# CustomIO.net
KiCad netlist of a schematic drawn in EAGLE
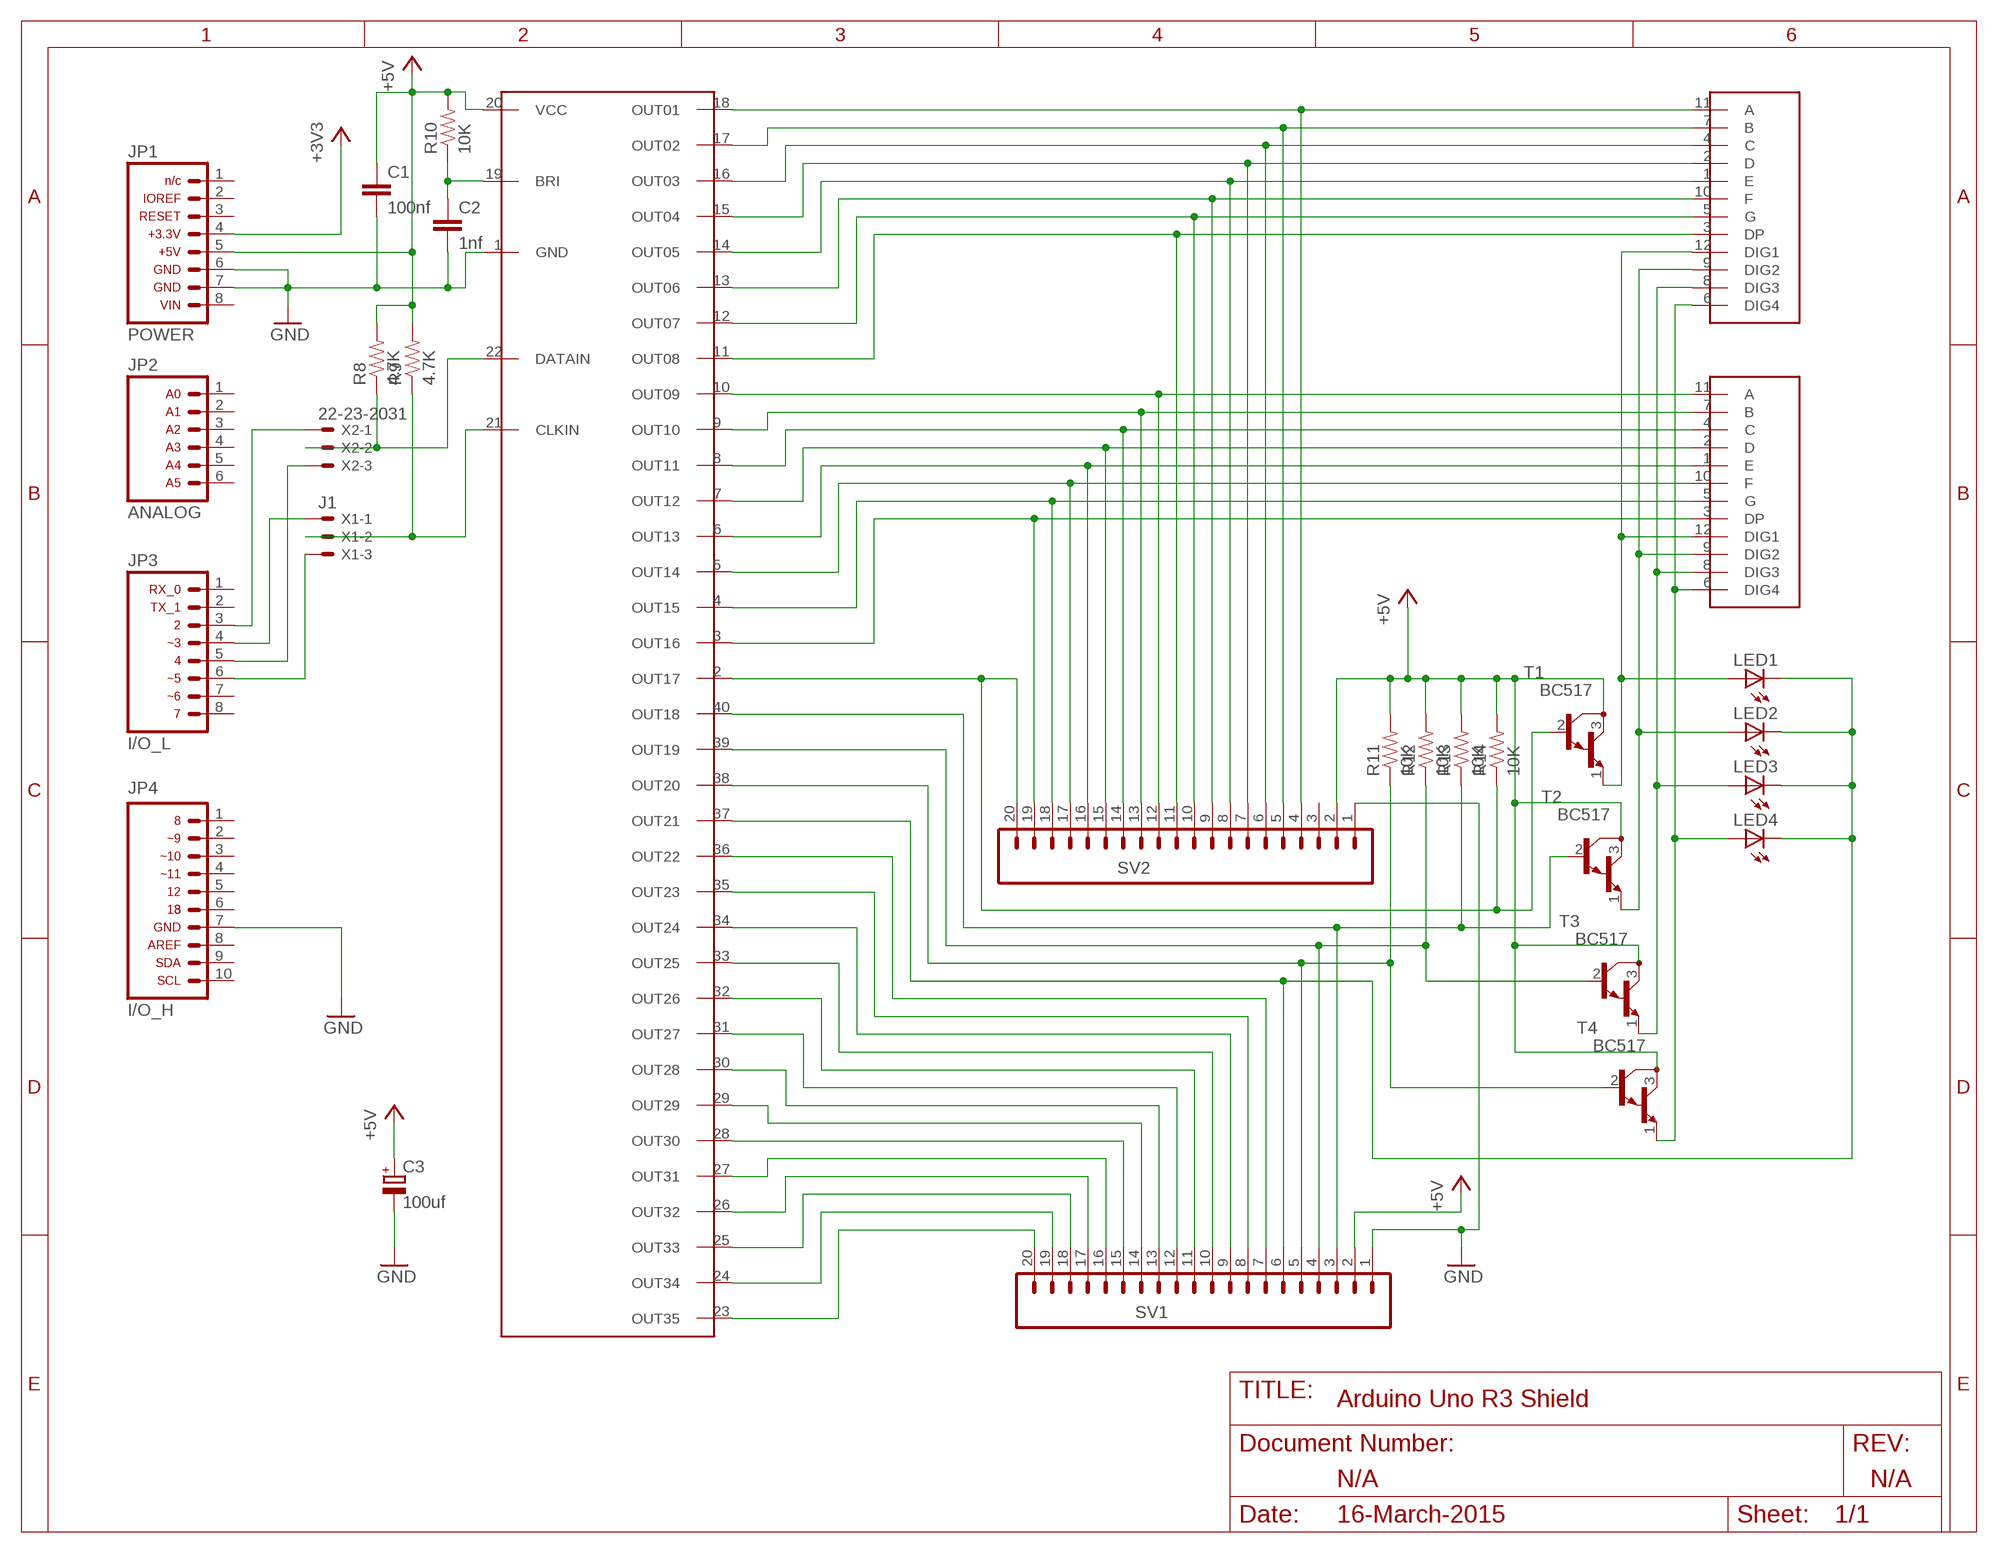
[diagram p0: schematic, sheet 1]

(export (version "E")
  (design (tool "Eeschema 10.0.6"))
  (components
    (comp (ref "C1")
      (value "100nf")
      (footprint "eagle-import:C2.5-4")
      (libsource (lib "eagle-import") (part "C2.5/4"))
    )
    (comp (ref "C2")
      (value "1nf")
      (footprint "eagle-import:C5B2.5")
      (libsource (lib "eagle-import") (part "C5/2.5"))
    )
    (comp (ref "C3")
      (value "100uf")
      (footprint "eagle-import:E2,5-7---100UF")
      (libsource (lib "eagle-import") (part "CPOL1"))
    )
    (comp (ref "JP1")
      (value "ARDUINO_CONN-POWERSIP")
      (footprint "eagle-import:CONN-1X08")
      (libsource (lib "eagle-import") (part "ARDUINO_CONN-POWERSIP"))
    )
    (comp (ref "JP2")
      (value "ARDUINO_CONN-ANALOGSIP")
      (footprint "eagle-import:CONN-1X06")
      (libsource (lib "eagle-import") (part "ARDUINO_CONN-ANALOGSIP"))
    )
    (comp (ref "JP3")
      (value "ARDUINO_CONN-IO_LSIP")
      (footprint "eagle-import:CONN-1X08")
      (libsource (lib "eagle-import") (part "ARDUINO_CONN-IO_LSIP"))
    )
    (comp (ref "JP4")
      (value "ARDUINO_CONN-IO_HSIP")
      (footprint "eagle-import:CONN-1X10")
      (libsource (lib "eagle-import") (part "ARDUINO_CONN-IO_HSIP"))
    )
    (comp (ref "LED1")
      (value "LED3MM")
      (footprint "eagle-import:HLMP-D105")
      (libsource (lib "eagle-import") (part "LED3MM"))
    )
    (comp (ref "LED2")
      (value "LED3MM")
      (footprint "eagle-import:HLMP-D105")
      (libsource (lib "eagle-import") (part "LED3MM"))
    )
    (comp (ref "LED3")
      (value "LED3MM")
      (footprint "eagle-import:HLMP-D105")
      (libsource (lib "eagle-import") (part "LED3MM"))
    )
    (comp (ref "LED4")
      (value "LED3MM")
      (footprint "eagle-import:HLMP-D105")
      (libsource (lib "eagle-import") (part "LED3MM"))
    )
    (comp (ref "R8")
      (value "4.7K")
      (footprint "eagle-import:AXIAL-0.3-KIT")
      (libsource (lib "eagle-import") (part "10KOHM1/6W5%(PTH)KIT"))
    )
    (comp (ref "R9")
      (value "4.7K")
      (footprint "eagle-import:AXIAL-0.3-KIT")
      (libsource (lib "eagle-import") (part "10KOHM1/6W5%(PTH)KIT"))
    )
    (comp (ref "R10")
      (value "10K")
      (footprint "eagle-import:AXIAL-0.3-KIT")
      (libsource (lib "eagle-import") (part "10KOHM1/6W5%(PTH)KIT"))
    )
    (comp (ref "R11")
      (value "10K")
      (footprint "eagle-import:AXIAL-0.3-KIT")
      (libsource (lib "eagle-import") (part "10KOHM1/6W5%(PTH)KIT"))
    )
    (comp (ref "R12")
      (value "10K")
      (footprint "eagle-import:AXIAL-0.3-KIT")
      (libsource (lib "eagle-import") (part "10KOHM1/6W5%(PTH)KIT"))
    )
    (comp (ref "R13")
      (value "10K")
      (footprint "eagle-import:AXIAL-0.3-KIT")
      (libsource (lib "eagle-import") (part "10KOHM1/6W5%(PTH)KIT"))
    )
    (comp (ref "R14")
      (value "10K")
      (footprint "eagle-import:AXIAL-0.3-KIT")
      (libsource (lib "eagle-import") (part "10KOHM1/6W5%(PTH)KIT"))
    )
    (comp (ref "SV1")
      (value "MA10-2")
      (footprint "eagle-import:MA10-2")
      (libsource (lib "eagle-import") (part "MA10-2"))
    )
    (comp (ref "SV2")
      (value "MA10-2")
      (footprint "eagle-import:MA10-2")
      (libsource (lib "eagle-import") (part "MA10-2"))
    )
    (comp (ref "T1")
      (value "BC517")
      (footprint "eagle-import:TO92")
      (libsource (lib "eagle-import") (part "BC517"))
    )
    (comp (ref "T2")
      (value "BC517")
      (footprint "eagle-import:TO92")
      (libsource (lib "eagle-import") (part "BC517"))
    )
    (comp (ref "T3")
      (value "BC517")
      (footprint "eagle-import:TO92")
      (libsource (lib "eagle-import") (part "BC517"))
    )
    (comp (ref "T4")
      (value "BC517")
      (footprint "eagle-import:TO92")
      (libsource (lib "eagle-import") (part "BC517"))
    )
    (comp (ref "U$1")
      (value "ST-M5451PDIP40")
      (footprint "eagle-import:DIL40")
      (libsource (lib "eagle-import") (part "ST-M5451PDIP40"))
    )
    (comp (ref "U$2")
      (value "LDS-3461BXTHURHOLE")
      (footprint "eagle-import:LDS-3461BX")
      (libsource (lib "eagle-import") (part "LDS-3461BXTHURHOLE"))
    )
    (comp (ref "U$3")
      (value "LDS-3461BXTHURHOLE")
      (footprint "eagle-import:LDS-3461BX")
      (libsource (lib "eagle-import") (part "LDS-3461BXTHURHOLE"))
    )
    (comp (ref "X1")
      (value "J1")
      (footprint "eagle-import:22-23-2031")
      (fields (field (name "MF") "MOLEX") (field (name "MPN") "22-23-2031"))
      (libsource (lib "eagle-import") (part "22-23-2031"))
    )
    (comp (ref "X2")
      (value "22-23-2031")
      (footprint "eagle-import:22-23-2031")
      (fields (field (name "MF") "MOLEX"))
      (libsource (lib "eagle-import") (part "22-23-2031"))
    )
  )
  (nets
    (net (code "1") (name "+3V3") (class "Default")
      (node (ref "JP1") (pin "4") (pinfunction "4_4") (pintype "passive"))
    )
    (net (code "2") (name "+5V") (class "Default")
      (node (ref "C1") (pin "1") (pinfunction "1_1") (pintype "passive"))
      (node (ref "C3") (pin "+") (pinfunction "+_+") (pintype "passive"))
      (node (ref "JP1") (pin "5") (pinfunction "5_5") (pintype "passive"))
      (node (ref "R10") (pin "P$2") (pinfunction "2_P$2") (pintype "passive"))
      (node (ref "R11") (pin "P$2") (pinfunction "2_P$2") (pintype "passive"))
      (node (ref "R12") (pin "P$2") (pinfunction "2_P$2") (pintype "passive"))
      (node (ref "R13") (pin "P$2") (pinfunction "2_P$2") (pintype "passive"))
      (node (ref "R14") (pin "P$2") (pinfunction "2_P$2") (pintype "passive"))
      (node (ref "R8") (pin "P$2") (pinfunction "2_P$2") (pintype "passive"))
      (node (ref "R9") (pin "P$2") (pinfunction "2_P$2") (pintype "passive"))
      (node (ref "SV1") (pin "2") (pinfunction "2_2") (pintype "passive"))
      (node (ref "SV2") (pin "2") (pinfunction "2_2") (pintype "passive"))
      (node (ref "T1") (pin "3") (pinfunction "C_3") (pintype "passive"))
      (node (ref "T2") (pin "3") (pinfunction "C_3") (pintype "passive"))
      (node (ref "T3") (pin "3") (pinfunction "C_3") (pintype "passive"))
      (node (ref "T4") (pin "3") (pinfunction "C_3") (pintype "passive"))
      (node (ref "U$1") (pin "20") (pinfunction "VCC_20") (pintype "bidirectional"))
    )
    (net (code "3") (name "GND") (class "Default")
      (node (ref "C1") (pin "2") (pinfunction "2_2") (pintype "passive"))
      (node (ref "C2") (pin "2") (pinfunction "2_2") (pintype "passive"))
      (node (ref "C3") (pin "-") (pinfunction "-_-") (pintype "passive"))
      (node (ref "JP1") (pin "6") (pinfunction "6_6") (pintype "passive"))
      (node (ref "JP1") (pin "7") (pinfunction "7_7") (pintype "passive"))
      (node (ref "JP4") (pin "7") (pinfunction "7_7") (pintype "passive"))
      (node (ref "SV1") (pin "1") (pinfunction "1_1") (pintype "passive"))
      (node (ref "SV2") (pin "1") (pinfunction "1_1") (pintype "passive"))
      (node (ref "U$1") (pin "1") (pinfunction "GND_1") (pintype "bidirectional"))
    )
    (net (code "4") (name "Net-(LED1-C)") (class "Default")
      (node (ref "LED1") (pin "K") (pinfunction "C_K") (pintype "passive"))
      (node (ref "LED2") (pin "K") (pinfunction "C_K") (pintype "passive"))
      (node (ref "LED3") (pin "K") (pinfunction "C_K") (pintype "passive"))
      (node (ref "LED4") (pin "K") (pinfunction "C_K") (pintype "passive"))
      (node (ref "SV1") (pin "6") (pinfunction "6_6") (pintype "passive"))
      (node (ref "U$1") (pin "37") (pinfunction "OUT21_37") (pintype "bidirectional"))
    )
    (net (code "5") (name "Net-(R8-1)") (class "Default")
      (node (ref "R8") (pin "P$1") (pinfunction "1_P$1") (pintype "passive"))
      (node (ref "U$1") (pin "22") (pinfunction "DATAIN_22") (pintype "bidirectional"))
      (node (ref "X2") (pin "2") (pinfunction "S_2") (pintype "passive"))
    )
    (net (code "6") (name "Net-(R9-1)") (class "Default")
      (node (ref "R9") (pin "P$1") (pinfunction "1_P$1") (pintype "passive"))
      (node (ref "U$1") (pin "21") (pinfunction "CLKIN_21") (pintype "bidirectional"))
      (node (ref "X1") (pin "2") (pinfunction "S_2") (pintype "passive"))
    )
    (net (code "7") (name "Net-(R10-1)") (class "Default")
      (node (ref "C2") (pin "1") (pinfunction "1_1") (pintype "passive"))
      (node (ref "R10") (pin "P$1") (pinfunction "1_P$1") (pintype "passive"))
      (node (ref "U$1") (pin "19") (pinfunction "BRI_19") (pintype "bidirectional"))
    )
    (net (code "8") (name "Net-(R11-1)") (class "Default")
      (node (ref "R11") (pin "P$1") (pinfunction "1_P$1") (pintype "passive"))
      (node (ref "SV1") (pin "5") (pinfunction "5_5") (pintype "passive"))
      (node (ref "T4") (pin "2") (pinfunction "B_2") (pintype "passive"))
      (node (ref "U$1") (pin "38") (pinfunction "OUT20_38") (pintype "bidirectional"))
    )
    (net (code "9") (name "Net-(R12-1)") (class "Default")
      (node (ref "R12") (pin "P$1") (pinfunction "1_P$1") (pintype "passive"))
      (node (ref "SV1") (pin "4") (pinfunction "4_4") (pintype "passive"))
      (node (ref "T3") (pin "2") (pinfunction "B_2") (pintype "passive"))
      (node (ref "U$1") (pin "39") (pinfunction "OUT19_39") (pintype "bidirectional"))
    )
    (net (code "10") (name "Net-(R13-1)") (class "Default")
      (node (ref "R13") (pin "P$1") (pinfunction "1_P$1") (pintype "passive"))
      (node (ref "SV1") (pin "3") (pinfunction "3_3") (pintype "passive"))
      (node (ref "T2") (pin "2") (pinfunction "B_2") (pintype "passive"))
      (node (ref "U$1") (pin "40") (pinfunction "OUT18_40") (pintype "bidirectional"))
    )
    (net (code "11") (name "Net-(R14-1)") (class "Default")
      (node (ref "R14") (pin "P$1") (pinfunction "1_P$1") (pintype "passive"))
      (node (ref "SV2") (pin "20") (pinfunction "20_20") (pintype "passive"))
      (node (ref "T1") (pin "2") (pinfunction "B_2") (pintype "passive"))
      (node (ref "U$1") (pin "2") (pinfunction "OUT17_2") (pintype "bidirectional"))
    )
    (net (code "12") (name "Net-(T1-E)") (class "Default")
      (node (ref "LED1") (pin "A") (pinfunction "A_A") (pintype "passive"))
      (node (ref "T1") (pin "1") (pinfunction "E_1") (pintype "passive"))
      (node (ref "U$2") (pin "12") (pinfunction "DIG1_12") (pintype "bidirectional"))
      (node (ref "U$3") (pin "12") (pinfunction "DIG1_12") (pintype "bidirectional"))
    )
    (net (code "13") (name "Net-(T2-E)") (class "Default")
      (node (ref "LED2") (pin "A") (pinfunction "A_A") (pintype "passive"))
      (node (ref "T2") (pin "1") (pinfunction "E_1") (pintype "passive"))
      (node (ref "U$2") (pin "9") (pinfunction "DIG2_9") (pintype "bidirectional"))
      (node (ref "U$3") (pin "9") (pinfunction "DIG2_9") (pintype "bidirectional"))
    )
    (net (code "14") (name "Net-(T3-E)") (class "Default")
      (node (ref "LED3") (pin "A") (pinfunction "A_A") (pintype "passive"))
      (node (ref "T3") (pin "1") (pinfunction "E_1") (pintype "passive"))
      (node (ref "U$2") (pin "8") (pinfunction "DIG3_8") (pintype "bidirectional"))
      (node (ref "U$3") (pin "8") (pinfunction "DIG3_8") (pintype "bidirectional"))
    )
    (net (code "15") (name "Net-(T4-E)") (class "Default")
      (node (ref "LED4") (pin "A") (pinfunction "A_A") (pintype "passive"))
      (node (ref "T4") (pin "1") (pinfunction "E_1") (pintype "passive"))
      (node (ref "U$2") (pin "6") (pinfunction "DIG4_6") (pintype "bidirectional"))
      (node (ref "U$3") (pin "6") (pinfunction "DIG4_6") (pintype "bidirectional"))
    )
    (net (code "16") (name "Net-(U$1C-OUT01)") (class "Default")
      (node (ref "SV2") (pin "4") (pinfunction "4_4") (pintype "passive"))
      (node (ref "U$1") (pin "18") (pinfunction "OUT01_18") (pintype "bidirectional"))
      (node (ref "U$2") (pin "11") (pinfunction "A_11") (pintype "bidirectional"))
    )
    (net (code "17") (name "Net-(U$1C-OUT02)") (class "Default")
      (node (ref "SV2") (pin "5") (pinfunction "5_5") (pintype "passive"))
      (node (ref "U$1") (pin "17") (pinfunction "OUT02_17") (pintype "bidirectional"))
      (node (ref "U$2") (pin "7") (pinfunction "B_7") (pintype "bidirectional"))
    )
    (net (code "18") (name "Net-(U$1C-OUT03)") (class "Default")
      (node (ref "SV2") (pin "6") (pinfunction "6_6") (pintype "passive"))
      (node (ref "U$1") (pin "16") (pinfunction "OUT03_16") (pintype "bidirectional"))
      (node (ref "U$2") (pin "4") (pinfunction "C_4") (pintype "bidirectional"))
    )
    (net (code "19") (name "Net-(U$1C-OUT04)") (class "Default")
      (node (ref "SV2") (pin "7") (pinfunction "7_7") (pintype "passive"))
      (node (ref "U$1") (pin "15") (pinfunction "OUT04_15") (pintype "bidirectional"))
      (node (ref "U$2") (pin "2") (pinfunction "D_2") (pintype "bidirectional"))
    )
    (net (code "20") (name "Net-(U$1C-OUT05)") (class "Default")
      (node (ref "SV2") (pin "8") (pinfunction "8_8") (pintype "passive"))
      (node (ref "U$1") (pin "14") (pinfunction "OUT05_14") (pintype "bidirectional"))
      (node (ref "U$2") (pin "1") (pinfunction "E_1") (pintype "bidirectional"))
    )
    (net (code "21") (name "Net-(U$1C-OUT06)") (class "Default")
      (node (ref "SV2") (pin "9") (pinfunction "9_9") (pintype "passive"))
      (node (ref "U$1") (pin "13") (pinfunction "OUT06_13") (pintype "bidirectional"))
      (node (ref "U$2") (pin "10") (pinfunction "F_10") (pintype "bidirectional"))
    )
    (net (code "22") (name "Net-(U$1C-OUT07)") (class "Default")
      (node (ref "SV2") (pin "10") (pinfunction "10_10") (pintype "passive"))
      (node (ref "U$1") (pin "12") (pinfunction "OUT07_12") (pintype "bidirectional"))
      (node (ref "U$2") (pin "5") (pinfunction "G_5") (pintype "bidirectional"))
    )
    (net (code "23") (name "Net-(U$1C-OUT08)") (class "Default")
      (node (ref "SV2") (pin "11") (pinfunction "11_11") (pintype "passive"))
      (node (ref "U$1") (pin "11") (pinfunction "OUT08_11") (pintype "bidirectional"))
      (node (ref "U$2") (pin "3") (pinfunction "DP_3") (pintype "bidirectional"))
    )
    (net (code "24") (name "Net-(U$1C-OUT09)") (class "Default")
      (node (ref "SV2") (pin "12") (pinfunction "12_12") (pintype "passive"))
      (node (ref "U$1") (pin "10") (pinfunction "OUT09_10") (pintype "bidirectional"))
      (node (ref "U$3") (pin "11") (pinfunction "A_11") (pintype "bidirectional"))
    )
    (net (code "25") (name "Net-(U$1C-OUT10)") (class "Default")
      (node (ref "SV2") (pin "13") (pinfunction "13_13") (pintype "passive"))
      (node (ref "U$1") (pin "9") (pinfunction "OUT10_9") (pintype "bidirectional"))
      (node (ref "U$3") (pin "7") (pinfunction "B_7") (pintype "bidirectional"))
    )
    (net (code "26") (name "Net-(U$1C-OUT11)") (class "Default")
      (node (ref "SV2") (pin "14") (pinfunction "14_14") (pintype "passive"))
      (node (ref "U$1") (pin "8") (pinfunction "OUT11_8") (pintype "bidirectional"))
      (node (ref "U$3") (pin "4") (pinfunction "C_4") (pintype "bidirectional"))
    )
    (net (code "27") (name "Net-(U$1C-OUT12)") (class "Default")
      (node (ref "SV2") (pin "15") (pinfunction "15_15") (pintype "passive"))
      (node (ref "U$1") (pin "7") (pinfunction "OUT12_7") (pintype "bidirectional"))
      (node (ref "U$3") (pin "2") (pinfunction "D_2") (pintype "bidirectional"))
    )
    (net (code "28") (name "Net-(U$1C-OUT13)") (class "Default")
      (node (ref "SV2") (pin "16") (pinfunction "16_16") (pintype "passive"))
      (node (ref "U$1") (pin "6") (pinfunction "OUT13_6") (pintype "bidirectional"))
      (node (ref "U$3") (pin "1") (pinfunction "E_1") (pintype "bidirectional"))
    )
    (net (code "29") (name "Net-(U$1C-OUT14)") (class "Default")
      (node (ref "SV2") (pin "17") (pinfunction "17_17") (pintype "passive"))
      (node (ref "U$1") (pin "5") (pinfunction "OUT14_5") (pintype "bidirectional"))
      (node (ref "U$3") (pin "10") (pinfunction "F_10") (pintype "bidirectional"))
    )
    (net (code "30") (name "Net-(U$1C-OUT15)") (class "Default")
      (node (ref "SV2") (pin "18") (pinfunction "18_18") (pintype "passive"))
      (node (ref "U$1") (pin "4") (pinfunction "OUT15_4") (pintype "bidirectional"))
      (node (ref "U$3") (pin "5") (pinfunction "G_5") (pintype "bidirectional"))
    )
    (net (code "31") (name "Net-(U$1C-OUT16)") (class "Default")
      (node (ref "SV2") (pin "19") (pinfunction "19_19") (pintype "passive"))
      (node (ref "U$1") (pin "3") (pinfunction "OUT16_3") (pintype "bidirectional"))
      (node (ref "U$3") (pin "3") (pinfunction "DP_3") (pintype "bidirectional"))
    )
    (net (code "32") (name "Net-(U$1C-OUT22)") (class "Default")
      (node (ref "SV1") (pin "7") (pinfunction "7_7") (pintype "passive"))
      (node (ref "U$1") (pin "36") (pinfunction "OUT22_36") (pintype "bidirectional"))
    )
    (net (code "33") (name "Net-(U$1C-OUT23)") (class "Default")
      (node (ref "SV1") (pin "8") (pinfunction "8_8") (pintype "passive"))
      (node (ref "U$1") (pin "35") (pinfunction "OUT23_35") (pintype "bidirectional"))
    )
    (net (code "34") (name "Net-(U$1C-OUT24)") (class "Default")
      (node (ref "SV1") (pin "9") (pinfunction "9_9") (pintype "passive"))
      (node (ref "U$1") (pin "34") (pinfunction "OUT24_34") (pintype "bidirectional"))
    )
    (net (code "35") (name "Net-(U$1C-OUT25)") (class "Default")
      (node (ref "SV1") (pin "10") (pinfunction "10_10") (pintype "passive"))
      (node (ref "U$1") (pin "33") (pinfunction "OUT25_33") (pintype "bidirectional"))
    )
    (net (code "36") (name "Net-(U$1C-OUT26)") (class "Default")
      (node (ref "SV1") (pin "11") (pinfunction "11_11") (pintype "passive"))
      (node (ref "U$1") (pin "32") (pinfunction "OUT26_32") (pintype "bidirectional"))
    )
    (net (code "37") (name "Net-(U$1C-OUT27)") (class "Default")
      (node (ref "SV1") (pin "12") (pinfunction "12_12") (pintype "passive"))
      (node (ref "U$1") (pin "31") (pinfunction "OUT27_31") (pintype "bidirectional"))
    )
    (net (code "38") (name "Net-(U$1C-OUT28)") (class "Default")
      (node (ref "SV1") (pin "13") (pinfunction "13_13") (pintype "passive"))
      (node (ref "U$1") (pin "30") (pinfunction "OUT28_30") (pintype "bidirectional"))
    )
    (net (code "39") (name "Net-(U$1C-OUT29)") (class "Default")
      (node (ref "SV1") (pin "14") (pinfunction "14_14") (pintype "passive"))
      (node (ref "U$1") (pin "29") (pinfunction "OUT29_29") (pintype "bidirectional"))
    )
    (net (code "40") (name "Net-(U$1C-OUT30)") (class "Default")
      (node (ref "SV1") (pin "15") (pinfunction "15_15") (pintype "passive"))
      (node (ref "U$1") (pin "28") (pinfunction "OUT30_28") (pintype "bidirectional"))
    )
    (net (code "41") (name "Net-(U$1C-OUT31)") (class "Default")
      (node (ref "SV1") (pin "16") (pinfunction "16_16") (pintype "passive"))
      (node (ref "U$1") (pin "27") (pinfunction "OUT31_27") (pintype "bidirectional"))
    )
    (net (code "42") (name "Net-(U$1C-OUT32)") (class "Default")
      (node (ref "SV1") (pin "17") (pinfunction "17_17") (pintype "passive"))
      (node (ref "U$1") (pin "26") (pinfunction "OUT32_26") (pintype "bidirectional"))
    )
    (net (code "43") (name "Net-(U$1C-OUT33)") (class "Default")
      (node (ref "SV1") (pin "18") (pinfunction "18_18") (pintype "passive"))
      (node (ref "U$1") (pin "25") (pinfunction "OUT33_25") (pintype "bidirectional"))
    )
    (net (code "44") (name "Net-(U$1C-OUT34)") (class "Default")
      (node (ref "SV1") (pin "19") (pinfunction "19_19") (pintype "passive"))
      (node (ref "U$1") (pin "24") (pinfunction "OUT34_24") (pintype "bidirectional"))
    )
    (net (code "45") (name "Net-(U$1C-OUT35)") (class "Default")
      (node (ref "SV1") (pin "20") (pinfunction "20_20") (pintype "passive"))
      (node (ref "U$1") (pin "23") (pinfunction "OUT35_23") (pintype "bidirectional"))
    )
    (net (code "46") (name "Net-(X1A-S)") (class "Default")
      (node (ref "JP3") (pin "4") (pinfunction "4_4") (pintype "passive"))
      (node (ref "X1") (pin "1") (pinfunction "S_1") (pintype "passive"))
    )
    (net (code "47") (name "Net-(X1C-S)") (class "Default")
      (node (ref "JP3") (pin "6") (pinfunction "6_6") (pintype "passive"))
      (node (ref "X1") (pin "3") (pinfunction "S_3") (pintype "passive"))
    )
    (net (code "48") (name "Net-(X2A-S)") (class "Default")
      (node (ref "JP3") (pin "3") (pinfunction "3_3") (pintype "passive"))
      (node (ref "X2") (pin "1") (pinfunction "S_1") (pintype "passive"))
    )
    (net (code "49") (name "Net-(X2C-S)") (class "Default")
      (node (ref "JP3") (pin "5") (pinfunction "5_5") (pintype "passive"))
      (node (ref "X2") (pin "3") (pinfunction "S_3") (pintype "passive"))
    )
    (net (code "50") (name "unconnected-(JP1-Pad1)") (class "Default")
      (node (ref "JP1") (pin "1") (pinfunction "1_1") (pintype "passive"))
    )
    (net (code "51") (name "unconnected-(JP1-Pad2)") (class "Default")
      (node (ref "JP1") (pin "2") (pinfunction "2_2") (pintype "passive"))
    )
    (net (code "52") (name "unconnected-(JP1-Pad3)") (class "Default")
      (node (ref "JP1") (pin "3") (pinfunction "3_3") (pintype "passive"))
    )
    (net (code "53") (name "unconnected-(JP1-Pad8)") (class "Default")
      (node (ref "JP1") (pin "8") (pinfunction "8_8") (pintype "passive"))
    )
    (net (code "54") (name "unconnected-(JP2-Pad1)") (class "Default")
      (node (ref "JP2") (pin "1") (pinfunction "1_1") (pintype "passive"))
    )
    (net (code "55") (name "unconnected-(JP2-Pad2)") (class "Default")
      (node (ref "JP2") (pin "2") (pinfunction "2_2") (pintype "passive"))
    )
    (net (code "56") (name "unconnected-(JP2-Pad3)") (class "Default")
      (node (ref "JP2") (pin "3") (pinfunction "3_3") (pintype "passive"))
    )
    (net (code "57") (name "unconnected-(JP2-Pad4)") (class "Default")
      (node (ref "JP2") (pin "4") (pinfunction "4_4") (pintype "passive"))
    )
    (net (code "58") (name "unconnected-(JP2-Pad5)") (class "Default")
      (node (ref "JP2") (pin "5") (pinfunction "5_5") (pintype "passive"))
    )
    (net (code "59") (name "unconnected-(JP2-Pad6)") (class "Default")
      (node (ref "JP2") (pin "6") (pinfunction "6_6") (pintype "passive"))
    )
    (net (code "60") (name "unconnected-(JP3-Pad1)") (class "Default")
      (node (ref "JP3") (pin "1") (pinfunction "1_1") (pintype "passive"))
    )
    (net (code "61") (name "unconnected-(JP3-Pad2)") (class "Default")
      (node (ref "JP3") (pin "2") (pinfunction "2_2") (pintype "passive"))
    )
    (net (code "62") (name "unconnected-(JP3-Pad7)") (class "Default")
      (node (ref "JP3") (pin "7") (pinfunction "7_7") (pintype "passive"))
    )
    (net (code "63") (name "unconnected-(JP3-Pad8)") (class "Default")
      (node (ref "JP3") (pin "8") (pinfunction "8_8") (pintype "passive"))
    )
    (net (code "64") (name "unconnected-(JP4-Pad1)") (class "Default")
      (node (ref "JP4") (pin "1") (pinfunction "1_1") (pintype "passive"))
    )
    (net (code "65") (name "unconnected-(JP4-Pad2)") (class "Default")
      (node (ref "JP4") (pin "2") (pinfunction "2_2") (pintype "passive"))
    )
    (net (code "66") (name "unconnected-(JP4-Pad3)") (class "Default")
      (node (ref "JP4") (pin "3") (pinfunction "3_3") (pintype "passive"))
    )
    (net (code "67") (name "unconnected-(JP4-Pad4)") (class "Default")
      (node (ref "JP4") (pin "4") (pinfunction "4_4") (pintype "passive"))
    )
    (net (code "68") (name "unconnected-(JP4-Pad5)") (class "Default")
      (node (ref "JP4") (pin "5") (pinfunction "5_5") (pintype "passive"))
    )
    (net (code "69") (name "unconnected-(JP4-Pad6)") (class "Default")
      (node (ref "JP4") (pin "6") (pinfunction "6_6") (pintype "passive"))
    )
    (net (code "70") (name "unconnected-(JP4-Pad8)") (class "Default")
      (node (ref "JP4") (pin "8") (pinfunction "8_8") (pintype "passive"))
    )
    (net (code "71") (name "unconnected-(JP4-Pad9)") (class "Default")
      (node (ref "JP4") (pin "9") (pinfunction "9_9") (pintype "passive"))
    )
    (net (code "72") (name "unconnected-(JP4-Pad10)") (class "Default")
      (node (ref "JP4") (pin "10") (pinfunction "10_10") (pintype "passive"))
    )
    (net (code "73") (name "unconnected-(SV2-Pad3)") (class "Default")
      (node (ref "SV2") (pin "3") (pinfunction "3_3") (pintype "passive"))
    )
  )
)
